# ele02_at.net
KiCad netlist of a schematic drawn in EAGLE
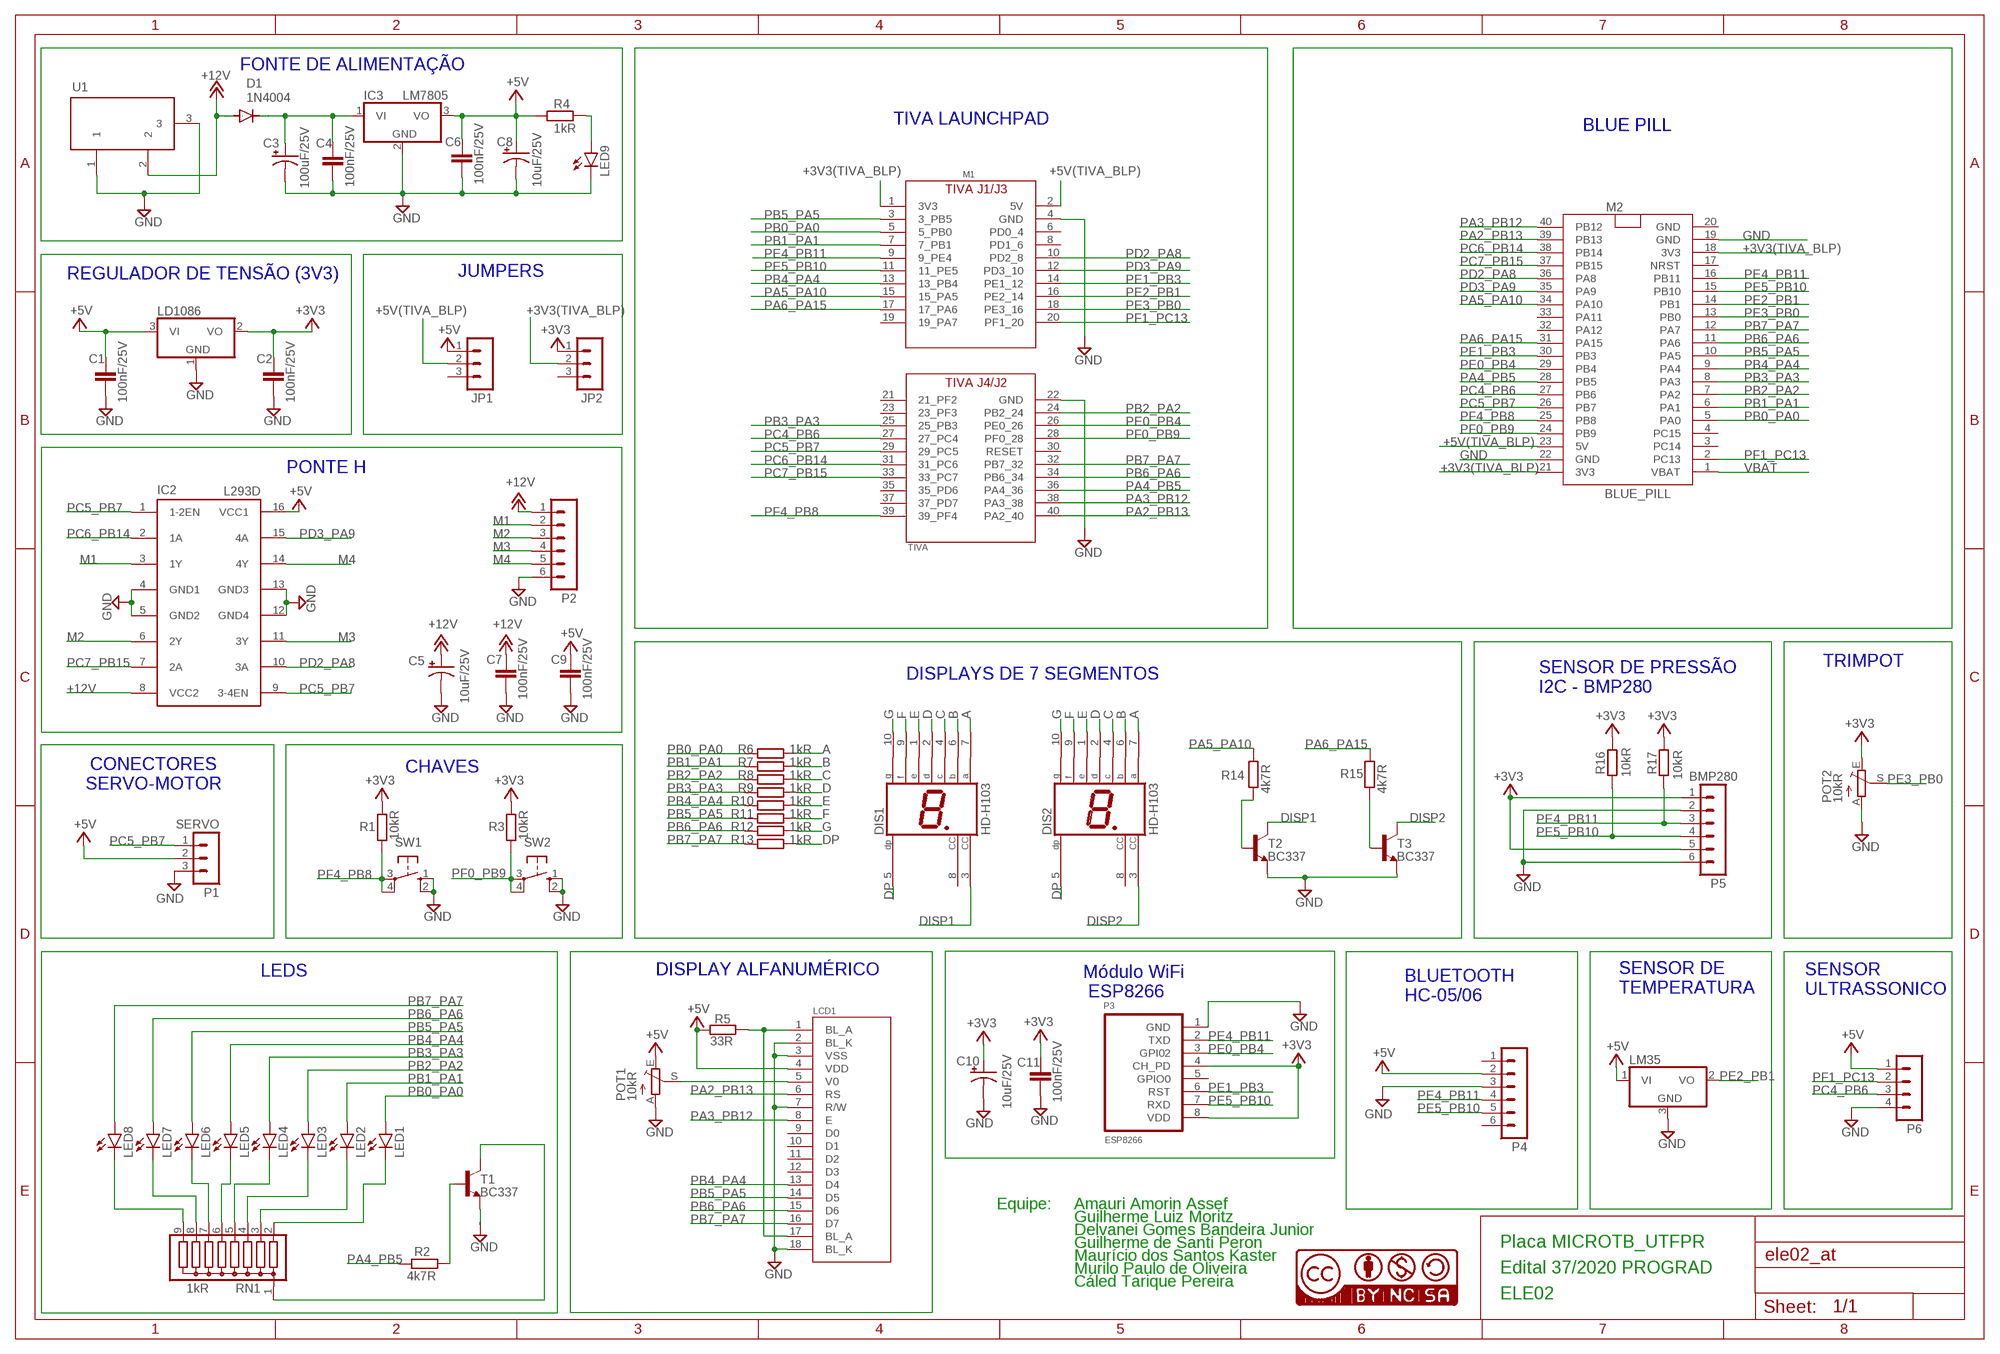
[diagram p0: schematic, sheet 1]

(export (version "E")
  (design (tool "Eeschema 10.0.6"))
  (components
    (comp (ref "C1")
      (value "100nF/25V")
      (footprint "eagle-import:C2.5-2")
      (libsource (lib "eagle-import") (part "C2.5/2"))
    )
    (comp (ref "C2")
      (value "100nF/25V")
      (footprint "eagle-import:C2.5-2")
      (libsource (lib "eagle-import") (part "C2.5/2"))
    )
    (comp (ref "C3")
      (value "100uF/25V")
      (footprint "eagle-import:E2,5-7")
      (libsource (lib "eagle-import") (part "CAPACITOR-PE2.5-7"))
    )
    (comp (ref "C4")
      (value "100nF/25V")
      (footprint "eagle-import:C2.5-2")
      (libsource (lib "eagle-import") (part "C2.5/2"))
    )
    (comp (ref "C5")
      (value "10uF/25V")
      (footprint "eagle-import:E2,5-6")
      (libsource (lib "eagle-import") (part "CAPACITOR-PE2.5-6"))
    )
    (comp (ref "C6")
      (value "100nF/25V")
      (footprint "eagle-import:C2.5-2")
      (libsource (lib "eagle-import") (part "C2.5/2"))
    )
    (comp (ref "C7")
      (value "100nF/25V")
      (footprint "eagle-import:C2.5-2")
      (libsource (lib "eagle-import") (part "C2.5/2"))
    )
    (comp (ref "C8")
      (value "10uF/25V")
      (footprint "eagle-import:E2,5-6")
      (libsource (lib "eagle-import") (part "CAPACITOR-PE2.5-6"))
    )
    (comp (ref "C9")
      (value "100nF/25V")
      (footprint "eagle-import:C2.5-2")
      (libsource (lib "eagle-import") (part "C2.5/2"))
    )
    (comp (ref "C10")
      (value "10uF/25V")
      (footprint "eagle-import:E2,5-6")
      (libsource (lib "eagle-import") (part "CAPACITOR-PE2.5-6"))
    )
    (comp (ref "C11")
      (value "100nF/25V")
      (footprint "eagle-import:C2.5-2")
      (libsource (lib "eagle-import") (part "C2.5/2"))
    )
    (comp (ref "D1")
      (value "1N4004")
      (footprint "eagle-import:DO41-10")
      (libsource (lib "eagle-import") (part "1N4004"))
    )
    (comp (ref "DIS1")
      (value "HD-H103")
      (footprint "eagle-import:HDSP-M")
      (libsource (lib "eagle-import") (part "HD-H103"))
    )
    (comp (ref "DIS2")
      (value "HD-H103")
      (footprint "eagle-import:HDSP-M")
      (libsource (lib "eagle-import") (part "HD-H103"))
    )
    (comp (ref "IC1")
      (value "LD1086")
      (footprint "eagle-import:LD1086")
      (libsource (lib "eagle-import") (part "LD1086TV05"))
    )
    (comp (ref "IC2")
      (value "L293D")
      (footprint "eagle-import:DIL16")
      (libsource (lib "eagle-import") (part "L293D"))
    )
    (comp (ref "IC3")
      (value "LM7805")
      (footprint "eagle-import:TO220V")
      (libsource (lib "eagle-import") (part "78TV6"))
    )
    (comp (ref "JP1")
      (value "JP")
      (footprint "eagle-import:MA03-1")
      (libsource (lib "eagle-import") (part "JUMP"))
    )
    (comp (ref "JP2")
      (value "JP")
      (footprint "eagle-import:MA03-1")
      (libsource (lib "eagle-import") (part "JUMP"))
    )
    (comp (ref "LCD1")
      (value "DISPLAY_LCDDISPLAY_LCD1")
      (footprint "eagle-import:DISPLAY_LCD_BL")
      (libsource (lib "eagle-import") (part "DISPLAY_LCDDISPLAY_LCD1"))
    )
    (comp (ref "LED1")
      (value "GREEN")
      (footprint "eagle-import:LED3MM")
      (libsource (lib "eagle-import") (part "LED3MM"))
    )
    (comp (ref "LED2")
      (value "GREEN")
      (footprint "eagle-import:LED3MM")
      (libsource (lib "eagle-import") (part "LED3MM"))
    )
    (comp (ref "LED3")
      (value "GREEN")
      (footprint "eagle-import:LED3MM")
      (libsource (lib "eagle-import") (part "LED3MM"))
    )
    (comp (ref "LED4")
      (value "GREEN")
      (footprint "eagle-import:LED3MM")
      (libsource (lib "eagle-import") (part "LED3MM"))
    )
    (comp (ref "LED5")
      (value "GREEN")
      (footprint "eagle-import:LED3MM")
      (libsource (lib "eagle-import") (part "LED3MM"))
    )
    (comp (ref "LED6")
      (value "GREEN")
      (footprint "eagle-import:LED3MM")
      (libsource (lib "eagle-import") (part "LED3MM"))
    )
    (comp (ref "LED7")
      (value "GREEN")
      (footprint "eagle-import:LED3MM")
      (libsource (lib "eagle-import") (part "LED3MM"))
    )
    (comp (ref "LED8")
      (value "GREEN")
      (footprint "eagle-import:LED3MM")
      (libsource (lib "eagle-import") (part "LED3MM"))
    )
    (comp (ref "LED9")
      (value "RED")
      (footprint "eagle-import:LED3MM")
      (libsource (lib "eagle-import") (part "LED3MM"))
    )
    (comp (ref "M1")
      (value "TIVA")
      (footprint "eagle-import:TIVA")
      (libsource (lib "eagle-import") (part "TIVA"))
    )
    (comp (ref "M2")
      (value "BLUE_PILL")
      (footprint "eagle-import:BLUE_PILL")
      (libsource (lib "eagle-import") (part "BLUE_PILL"))
    )
    (comp (ref "P1")
      (value "SERVO")
      (footprint "eagle-import:MA03-1")
      (libsource (lib "eagle-import") (part "CON3"))
    )
    (comp (ref "P2")
      (value "Motor")
      (footprint "eagle-import:HC_BLUETOOTH")
      (libsource (lib "eagle-import") (part "MA06-1"))
    )
    (comp (ref "P3")
      (value "ESP8266")
      (footprint "eagle-import:ESP8266")
      (libsource (lib "eagle-import") (part "ESP8266"))
    )
    (comp (ref "P4")
      (value "HC05_06")
      (footprint "eagle-import:HC_BLUETOOTH")
      (libsource (lib "eagle-import") (part "HC05_06"))
    )
    (comp (ref "P5")
      (value "BMP280")
      (footprint "eagle-import:BMP280")
      (libsource (lib "eagle-import") (part "BMP280"))
    )
    (comp (ref "P6")
      (value "HC-04")
      (footprint "eagle-import:HS-04")
      (libsource (lib "eagle-import") (part "HC-SR04US"))
    )
    (comp (ref "POT1")
      (value "10kR")
      (footprint "eagle-import:CA6V")
      (libsource (lib "eagle-import") (part "TRIM_EU-ELE02CA6V"))
    )
    (comp (ref "POT2")
      (value "10kR")
      (footprint "eagle-import:CIP20C-4MM")
      (libsource (lib "eagle-import") (part "TRIM_EU-CIP20C-4MM"))
    )
    (comp (ref "Q1")
      (value "LM35L05Z")
      (footprint "eagle-import:LM35")
      (libsource (lib "eagle-import") (part "LM35ZL05"))
    )
    (comp (ref "R1")
      (value "10kR")
      (footprint "eagle-import:0204_7")
      (libsource (lib "eagle-import") (part "R-EU_0204/7"))
    )
    (comp (ref "R2")
      (value "4k7R")
      (footprint "eagle-import:0204_7")
      (libsource (lib "eagle-import") (part "R-EU_0204/7"))
    )
    (comp (ref "R3")
      (value "10kR")
      (footprint "eagle-import:0204_7")
      (libsource (lib "eagle-import") (part "R-EU_0204/7"))
    )
    (comp (ref "R4")
      (value "1kR")
      (footprint "eagle-import:0204_7")
      (libsource (lib "eagle-import") (part "R-EU_0204/7"))
    )
    (comp (ref "R5")
      (value "33R")
      (footprint "eagle-import:0204_7")
      (libsource (lib "eagle-import") (part "R-EU_0204/7"))
    )
    (comp (ref "R6")
      (value "1kR")
      (footprint "eagle-import:0204_7")
      (libsource (lib "eagle-import") (part "R-EU_0204/7"))
    )
    (comp (ref "R7")
      (value "1kR")
      (footprint "eagle-import:0204_7")
      (libsource (lib "eagle-import") (part "R-EU_0204/7"))
    )
    (comp (ref "R8")
      (value "1kR")
      (footprint "eagle-import:0204_7")
      (libsource (lib "eagle-import") (part "R-EU_0204/7"))
    )
    (comp (ref "R9")
      (value "1kR")
      (footprint "eagle-import:0204_7")
      (libsource (lib "eagle-import") (part "R-EU_0204/7"))
    )
    (comp (ref "R10")
      (value "1kR")
      (footprint "eagle-import:0204_7")
      (libsource (lib "eagle-import") (part "R-EU_0204/7"))
    )
    (comp (ref "R11")
      (value "1kR")
      (footprint "eagle-import:0204_7")
      (libsource (lib "eagle-import") (part "R-EU_0204/7"))
    )
    (comp (ref "R12")
      (value "1kR")
      (footprint "eagle-import:0204_7")
      (libsource (lib "eagle-import") (part "R-EU_0204/7"))
    )
    (comp (ref "R13")
      (value "1kR")
      (footprint "eagle-import:0204_7")
      (libsource (lib "eagle-import") (part "R-EU_0204/7"))
    )
    (comp (ref "R14")
      (value "4k7R")
      (footprint "eagle-import:0204_7")
      (libsource (lib "eagle-import") (part "R-EU_0204/7"))
    )
    (comp (ref "R15")
      (value "4k7R")
      (footprint "eagle-import:0204_7")
      (libsource (lib "eagle-import") (part "R-EU_0204/7"))
    )
    (comp (ref "R16")
      (value "10kR")
      (footprint "eagle-import:0204_7")
      (libsource (lib "eagle-import") (part "R-EU_0204/7"))
    )
    (comp (ref "R17")
      (value "10kR")
      (footprint "eagle-import:0204_7")
      (libsource (lib "eagle-import") (part "R-EU_0204/7"))
    )
    (comp (ref "RN1")
      (value "1kR")
      (footprint "eagle-import:SIL9")
      (libsource (lib "eagle-import") (part "G08R"))
    )
    (comp (ref "SW1")
      (value "SW")
      (footprint "eagle-import:B3F-10XX")
      (fields (field (name "MPN") "B3F-1000"))
      (libsource (lib "eagle-import") (part "10-XX"))
    )
    (comp (ref "SW2")
      (value "SW")
      (footprint "eagle-import:B3F-10XX")
      (fields (field (name "MPN") "B3F-1000"))
      (libsource (lib "eagle-import") (part "10-XX"))
    )
    (comp (ref "T1")
      (value "BC337")
      (footprint "eagle-import:TO92-CBE")
      (libsource (lib "eagle-import") (part "-NPN-TO92-CBEBC337-16"))
    )
    (comp (ref "T2")
      (value "BC337")
      (footprint "eagle-import:TO92-CBE")
      (libsource (lib "eagle-import") (part "-NPN-TO92-CBEBC337-16"))
    )
    (comp (ref "T3")
      (value "BC337")
      (footprint "eagle-import:TO92-CBE")
      (libsource (lib "eagle-import") (part "-NPN-TO92-CBEBC337-16"))
    )
    (comp (ref "U$1")
      (value "CC-NC-BC")
      (footprint "eagle-import:CC-NC-BY")
      (libsource (lib "eagle-import") (part "CC-NC-BC"))
    )
    (comp (ref "U1")
      (value "POWERSUPPLY_DC21MMX")
      (footprint "eagle-import:POWERSUPPLY_DC-21MM")
      (libsource (lib "eagle-import") (part "POWERSUPPLY_DC21MMX"))
    )
  )
  (nets
    (net (code "1") (name "+3V3") (class "Default")
      (node (ref "C10") (pin "+") (pinfunction "+_+") (pintype "passive"))
      (node (ref "C11") (pin "1") (pinfunction "1_1") (pintype "passive"))
      (node (ref "C2") (pin "1") (pinfunction "1_1") (pintype "passive"))
      (node (ref "IC1") (pin "2") (pinfunction "VO_2") (pintype "passive"))
      (node (ref "JP2") (pin "1") (pinfunction "1_1") (pintype "passive"))
      (node (ref "P3") (pin "4") (pinfunction "CH_PD_4") (pintype "bidirectional"))
      (node (ref "P3") (pin "8") (pinfunction "VDD_8") (pintype "bidirectional"))
      (node (ref "P5") (pin "1") (pinfunction "1_1") (pintype "passive"))
      (node (ref "P5") (pin "5") (pinfunction "5_5") (pintype "passive"))
      (node (ref "POT2") (pin "E") (pinfunction "E_E") (pintype "passive"))
      (node (ref "R1") (pin "2") (pinfunction "2_2") (pintype "passive"))
      (node (ref "R16") (pin "2") (pinfunction "2_2") (pintype "passive"))
      (node (ref "R17") (pin "2") (pinfunction "2_2") (pintype "passive"))
      (node (ref "R3") (pin "2") (pinfunction "2_2") (pintype "passive"))
    )
    (net (code "2") (name "+5V") (class "Default")
      (node (ref "C1") (pin "1") (pinfunction "1_1") (pintype "passive"))
      (node (ref "C6") (pin "1") (pinfunction "1_1") (pintype "passive"))
      (node (ref "C8") (pin "+") (pinfunction "+_+") (pintype "passive"))
      (node (ref "C9") (pin "1") (pinfunction "1_1") (pintype "passive"))
      (node (ref "IC1") (pin "3") (pinfunction "VI_3") (pintype "input"))
      (node (ref "IC2") (pin "16") (pinfunction "VCC1_16") (pintype "power_in"))
      (node (ref "IC3") (pin "3") (pinfunction "VO_3") (pintype "passive"))
      (node (ref "JP1") (pin "1") (pinfunction "1_1") (pintype "passive"))
      (node (ref "LCD1") (pin "4") (pinfunction "VDD_4") (pintype "bidirectional"))
      (node (ref "P1") (pin "2") (pinfunction "2_2") (pintype "passive"))
      (node (ref "P4") (pin "2") (pinfunction "2_2") (pintype "passive"))
      (node (ref "P6") (pin "1") (pinfunction "1_1") (pintype "passive"))
      (node (ref "POT1") (pin "E") (pinfunction "E_E") (pintype "passive"))
      (node (ref "Q1") (pin "1") (pinfunction "VI_1") (pintype "input"))
      (node (ref "R4") (pin "1") (pinfunction "1_1") (pintype "passive"))
      (node (ref "R5") (pin "2") (pinfunction "2_2") (pintype "passive"))
    )
    (net (code "3") (name "+12V") (class "Default")
      (node (ref "C5") (pin "+") (pinfunction "+_+") (pintype "passive"))
      (node (ref "C7") (pin "1") (pinfunction "1_1") (pintype "passive"))
      (node (ref "D1") (pin "A") (pinfunction "A_A") (pintype "passive"))
      (node (ref "IC2") (pin "8") (pinfunction "VCC2_8") (pintype "power_in"))
      (node (ref "P2") (pin "1") (pinfunction "1_1") (pintype "passive"))
      (node (ref "U1") (pin "2") (pinfunction "2_2") (pintype "power_in"))
    )
    (net (code "4") (name "/+3V3(TIVA_BLP)") (class "Default")
      (node (ref "JP2") (pin "2") (pinfunction "2_2") (pintype "passive"))
      (node (ref "M1") (pin "1") (pinfunction "3V3_1") (pintype "bidirectional"))
      (node (ref "M2") (pin "18") (pinfunction "3V3_18") (pintype "bidirectional"))
      (node (ref "M2") (pin "21") (pinfunction "3V3_21") (pintype "bidirectional"))
    )
    (net (code "5") (name "/+5V(TIVA_BLP)") (class "Default")
      (node (ref "JP1") (pin "2") (pinfunction "2_2") (pintype "passive"))
      (node (ref "M1") (pin "2") (pinfunction "5V_2") (pintype "bidirectional"))
      (node (ref "M2") (pin "23") (pinfunction "5V_23") (pintype "bidirectional"))
    )
    (net (code "6") (name "/A") (class "Default")
      (node (ref "DIS1") (pin "7") (pinfunction "A_7") (pintype "passive"))
      (node (ref "DIS2") (pin "7") (pinfunction "A_7") (pintype "passive"))
      (node (ref "R6") (pin "1") (pinfunction "1_1") (pintype "passive"))
    )
    (net (code "7") (name "/B") (class "Default")
      (node (ref "DIS1") (pin "6") (pinfunction "B_6") (pintype "passive"))
      (node (ref "DIS2") (pin "6") (pinfunction "B_6") (pintype "passive"))
      (node (ref "R7") (pin "1") (pinfunction "1_1") (pintype "passive"))
    )
    (net (code "8") (name "/C") (class "Default")
      (node (ref "DIS1") (pin "4") (pinfunction "C_4") (pintype "passive"))
      (node (ref "DIS2") (pin "4") (pinfunction "C_4") (pintype "passive"))
      (node (ref "R8") (pin "1") (pinfunction "1_1") (pintype "passive"))
    )
    (net (code "9") (name "/D") (class "Default")
      (node (ref "DIS1") (pin "2") (pinfunction "D_2") (pintype "passive"))
      (node (ref "DIS2") (pin "2") (pinfunction "D_2") (pintype "passive"))
      (node (ref "R9") (pin "1") (pinfunction "1_1") (pintype "passive"))
    )
    (net (code "10") (name "/DISP1") (class "Default")
      (node (ref "DIS1") (pin "3") (pinfunction "CC_3") (pintype "passive"))
      (node (ref "T2") (pin "C") (pinfunction "C_C") (pintype "passive"))
    )
    (net (code "11") (name "/DISP2") (class "Default")
      (node (ref "DIS2") (pin "3") (pinfunction "CC_3") (pintype "passive"))
      (node (ref "T3") (pin "C") (pinfunction "C_C") (pintype "passive"))
    )
    (net (code "12") (name "/DP") (class "Default")
      (node (ref "DIS1") (pin "5") (pinfunction "DP_5") (pintype "passive"))
      (node (ref "DIS2") (pin "5") (pinfunction "DP_5") (pintype "passive"))
      (node (ref "R13") (pin "1") (pinfunction "1_1") (pintype "passive"))
    )
    (net (code "13") (name "/E") (class "Default")
      (node (ref "DIS1") (pin "1") (pinfunction "E_1") (pintype "passive"))
      (node (ref "DIS2") (pin "1") (pinfunction "E_1") (pintype "passive"))
      (node (ref "R10") (pin "1") (pinfunction "1_1") (pintype "passive"))
    )
    (net (code "14") (name "/F") (class "Default")
      (node (ref "DIS1") (pin "9") (pinfunction "F_9") (pintype "passive"))
      (node (ref "DIS2") (pin "9") (pinfunction "F_9") (pintype "passive"))
      (node (ref "R11") (pin "1") (pinfunction "1_1") (pintype "passive"))
    )
    (net (code "15") (name "/G") (class "Default")
      (node (ref "DIS1") (pin "10") (pinfunction "G_10") (pintype "passive"))
      (node (ref "DIS2") (pin "10") (pinfunction "G_10") (pintype "passive"))
      (node (ref "R12") (pin "1") (pinfunction "1_1") (pintype "passive"))
    )
    (net (code "16") (name "/M1") (class "Default")
      (node (ref "IC2") (pin "3") (pinfunction "1Y_3") (pintype "output"))
      (node (ref "P2") (pin "2") (pinfunction "2_2") (pintype "passive"))
    )
    (net (code "17") (name "/M2") (class "Default")
      (node (ref "IC2") (pin "6") (pinfunction "2Y_6") (pintype "output"))
      (node (ref "P2") (pin "3") (pinfunction "3_3") (pintype "passive"))
    )
    (net (code "18") (name "/M3") (class "Default")
      (node (ref "IC2") (pin "11") (pinfunction "3Y_11") (pintype "output"))
      (node (ref "P2") (pin "4") (pinfunction "4_4") (pintype "passive"))
    )
    (net (code "19") (name "/M4") (class "Default")
      (node (ref "IC2") (pin "14") (pinfunction "4Y_14") (pintype "output"))
      (node (ref "P2") (pin "5") (pinfunction "5_5") (pintype "passive"))
    )
    (net (code "20") (name "/PA2_PB13") (class "Default")
      (node (ref "LCD1") (pin "6") (pinfunction "RS_6") (pintype "bidirectional"))
      (node (ref "M1") (pin "40") (pinfunction "PA2_40_40") (pintype "bidirectional"))
      (node (ref "M2") (pin "39") (pinfunction "PB13_39") (pintype "bidirectional"))
    )
    (net (code "21") (name "/PA3_PB12") (class "Default")
      (node (ref "LCD1") (pin "8") (pinfunction "E_8") (pintype "bidirectional"))
      (node (ref "M1") (pin "38") (pinfunction "PA3_38_38") (pintype "input"))
      (node (ref "M2") (pin "40") (pinfunction "PB12_40") (pintype "bidirectional"))
    )
    (net (code "22") (name "/PA4_PB5") (class "Default")
      (node (ref "M1") (pin "36") (pinfunction "PA4_36_36") (pintype "input"))
      (node (ref "M2") (pin "28") (pinfunction "PB5_28") (pintype "bidirectional"))
      (node (ref "R2") (pin "1") (pinfunction "1_1") (pintype "passive"))
    )
    (net (code "23") (name "/PA5_PA10") (class "Default")
      (node (ref "M1") (pin "15") (pinfunction "15_PA5_15") (pintype "bidirectional"))
      (node (ref "M2") (pin "34") (pinfunction "PA10_34") (pintype "bidirectional"))
      (node (ref "R14") (pin "2") (pinfunction "2_2") (pintype "passive"))
    )
    (net (code "24") (name "/PA6_PA15") (class "Default")
      (node (ref "M1") (pin "17") (pinfunction "17_PA6_17") (pintype "bidirectional"))
      (node (ref "M2") (pin "31") (pinfunction "PA15_31") (pintype "bidirectional"))
      (node (ref "R15") (pin "2") (pinfunction "2_2") (pintype "passive"))
    )
    (net (code "25") (name "/PB0_PA0") (class "Default")
      (node (ref "LED1") (pin "A") (pinfunction "A_A") (pintype "passive"))
      (node (ref "M1") (pin "5") (pinfunction "5_PB0_5") (pintype "bidirectional"))
      (node (ref "M2") (pin "5") (pinfunction "PA0_5") (pintype "bidirectional"))
      (node (ref "R6") (pin "2") (pinfunction "2_2") (pintype "passive"))
    )
    (net (code "26") (name "/PB1_PA1") (class "Default")
      (node (ref "LED2") (pin "A") (pinfunction "A_A") (pintype "passive"))
      (node (ref "M1") (pin "7") (pinfunction "7_PB1_7") (pintype "bidirectional"))
      (node (ref "M2") (pin "6") (pinfunction "PA1_6") (pintype "bidirectional"))
      (node (ref "R7") (pin "2") (pinfunction "2_2") (pintype "passive"))
    )
    (net (code "27") (name "/PB2_PA2") (class "Default")
      (node (ref "LED3") (pin "A") (pinfunction "A_A") (pintype "passive"))
      (node (ref "M1") (pin "24") (pinfunction "PB2_24_24") (pintype "input"))
      (node (ref "M2") (pin "7") (pinfunction "PA2_7") (pintype "bidirectional"))
      (node (ref "R8") (pin "2") (pinfunction "2_2") (pintype "passive"))
    )
    (net (code "28") (name "/PB3_PA3") (class "Default")
      (node (ref "LED4") (pin "A") (pinfunction "A_A") (pintype "passive"))
      (node (ref "M1") (pin "25") (pinfunction "25_PB3_25") (pintype "bidirectional"))
      (node (ref "M2") (pin "8") (pinfunction "PA3_8") (pintype "bidirectional"))
      (node (ref "R9") (pin "2") (pinfunction "2_2") (pintype "passive"))
    )
    (net (code "29") (name "/PB4_PA4") (class "Default")
      (node (ref "LCD1") (pin "13") (pinfunction "D4_13") (pintype "bidirectional"))
      (node (ref "LED5") (pin "A") (pinfunction "A_A") (pintype "passive"))
      (node (ref "M1") (pin "13") (pinfunction "13_PB4_13") (pintype "bidirectional"))
      (node (ref "M2") (pin "9") (pinfunction "PA4_9") (pintype "bidirectional"))
      (node (ref "R10") (pin "2") (pinfunction "2_2") (pintype "passive"))
    )
    (net (code "30") (name "/PB5_PA5") (class "Default")
      (node (ref "LCD1") (pin "14") (pinfunction "D5_14") (pintype "bidirectional"))
      (node (ref "LED6") (pin "A") (pinfunction "A_A") (pintype "passive"))
      (node (ref "M1") (pin "3") (pinfunction "3_PB5_3") (pintype "bidirectional"))
      (node (ref "M2") (pin "10") (pinfunction "PA5_10") (pintype "bidirectional"))
      (node (ref "R11") (pin "2") (pinfunction "2_2") (pintype "passive"))
    )
    (net (code "31") (name "/PB6_PA6") (class "Default")
      (node (ref "LCD1") (pin "15") (pinfunction "D6_15") (pintype "bidirectional"))
      (node (ref "LED7") (pin "A") (pinfunction "A_A") (pintype "passive"))
      (node (ref "M1") (pin "34") (pinfunction "PB6_34_34") (pintype "bidirectional"))
      (node (ref "M2") (pin "11") (pinfunction "PA6_11") (pintype "bidirectional"))
      (node (ref "R12") (pin "2") (pinfunction "2_2") (pintype "passive"))
    )
    (net (code "32") (name "/PB7_PA7") (class "Default")
      (node (ref "LCD1") (pin "16") (pinfunction "D7_16") (pintype "bidirectional"))
      (node (ref "LED8") (pin "A") (pinfunction "A_A") (pintype "passive"))
      (node (ref "M1") (pin "32") (pinfunction "PB7_32_32") (pintype "bidirectional"))
      (node (ref "M2") (pin "12") (pinfunction "PA7_12") (pintype "bidirectional"))
      (node (ref "R13") (pin "2") (pinfunction "2_2") (pintype "passive"))
    )
    (net (code "33") (name "/PC4_PB6") (class "Default")
      (node (ref "M1") (pin "27") (pinfunction "27_PC4_27") (pintype "bidirectional"))
      (node (ref "M2") (pin "27") (pinfunction "PB6_27") (pintype "bidirectional"))
      (node (ref "P6") (pin "3") (pinfunction "3_3") (pintype "passive"))
    )
    (net (code "34") (name "/PC5_PB7") (class "Default")
      (node (ref "IC2") (pin "1") (pinfunction "1-2EN_1") (pintype "input"))
      (node (ref "IC2") (pin "9") (pinfunction "3-4EN_9") (pintype "input"))
      (node (ref "M1") (pin "29") (pinfunction "29_PC5_29") (pintype "input"))
      (node (ref "M2") (pin "26") (pinfunction "PB7_26") (pintype "bidirectional"))
      (node (ref "P1") (pin "1") (pinfunction "1_1") (pintype "passive"))
    )
    (net (code "35") (name "/PC6_PB14") (class "Default")
      (node (ref "IC2") (pin "2") (pinfunction "1A_2") (pintype "input"))
      (node (ref "M1") (pin "31") (pinfunction "31_PC6_31") (pintype "bidirectional"))
      (node (ref "M2") (pin "38") (pinfunction "PB14_38") (pintype "bidirectional"))
    )
    (net (code "36") (name "/PC7_PB15") (class "Default")
      (node (ref "IC2") (pin "7") (pinfunction "2A_7") (pintype "input"))
      (node (ref "M1") (pin "33") (pinfunction "33_PC7_33") (pintype "bidirectional"))
      (node (ref "M2") (pin "37") (pinfunction "PB15_37") (pintype "bidirectional"))
    )
    (net (code "37") (name "/PD2_PA8") (class "Default")
      (node (ref "IC2") (pin "10") (pinfunction "3A_10") (pintype "input"))
      (node (ref "M1") (pin "10") (pinfunction "PD2_8_10") (pintype "bidirectional"))
      (node (ref "M2") (pin "36") (pinfunction "PA8_36") (pintype "bidirectional"))
    )
    (net (code "38") (name "/PD3_PA9") (class "Default")
      (node (ref "IC2") (pin "15") (pinfunction "4A_15") (pintype "input"))
      (node (ref "M1") (pin "12") (pinfunction "PD3_10_12") (pintype "bidirectional"))
      (node (ref "M2") (pin "35") (pinfunction "PA9_35") (pintype "bidirectional"))
    )
    (net (code "39") (name "/PE0_PB4") (class "Default")
      (node (ref "M1") (pin "26") (pinfunction "PE0_26_26") (pintype "bidirectional"))
      (node (ref "M2") (pin "29") (pinfunction "PB4_29") (pintype "bidirectional"))
      (node (ref "P3") (pin "3") (pinfunction "GPI02_3") (pintype "bidirectional"))
    )
    (net (code "40") (name "/PE1_PB3") (class "Default")
      (node (ref "M1") (pin "14") (pinfunction "PE1_12_14") (pintype "bidirectional"))
      (node (ref "M2") (pin "30") (pinfunction "PB3_30") (pintype "bidirectional"))
      (node (ref "P3") (pin "6") (pinfunction "RST_6") (pintype "bidirectional"))
    )
    (net (code "41") (name "/PE2_PB1") (class "Default")
      (node (ref "M1") (pin "16") (pinfunction "PE2_14_16") (pintype "bidirectional"))
      (node (ref "M2") (pin "14") (pinfunction "PB1_14") (pintype "bidirectional"))
      (node (ref "Q1") (pin "2") (pinfunction "VO_2") (pintype "passive"))
    )
    (net (code "42") (name "/PE3_PB0") (class "Default")
      (node (ref "M1") (pin "18") (pinfunction "PE3_16_18") (pintype "bidirectional"))
      (node (ref "M2") (pin "13") (pinfunction "PB0_13") (pintype "bidirectional"))
      (node (ref "POT2") (pin "S") (pinfunction "S_S") (pintype "passive"))
    )
    (net (code "43") (name "/PE4_PB11") (class "Default")
      (node (ref "M1") (pin "9") (pinfunction "9_PE4_9") (pintype "bidirectional"))
      (node (ref "M2") (pin "16") (pinfunction "PB11_16") (pintype "bidirectional"))
      (node (ref "P3") (pin "2") (pinfunction "TXD_2") (pintype "bidirectional"))
      (node (ref "P4") (pin "4") (pinfunction "4_4") (pintype "passive"))
      (node (ref "P5") (pin "3") (pinfunction "3_3") (pintype "passive"))
      (node (ref "R17") (pin "1") (pinfunction "1_1") (pintype "passive"))
    )
    (net (code "44") (name "/PE5_PB10") (class "Default")
      (node (ref "M1") (pin "11") (pinfunction "11_PE5_11") (pintype "bidirectional"))
      (node (ref "M2") (pin "15") (pinfunction "PB10_15") (pintype "bidirectional"))
      (node (ref "P3") (pin "7") (pinfunction "RXD_7") (pintype "bidirectional"))
      (node (ref "P4") (pin "5") (pinfunction "5_5") (pintype "passive"))
      (node (ref "P5") (pin "4") (pinfunction "4_4") (pintype "passive"))
      (node (ref "R16") (pin "1") (pinfunction "1_1") (pintype "passive"))
    )
    (net (code "45") (name "/PF0_PB9") (class "Default")
      (node (ref "M1") (pin "28") (pinfunction "PF0_28_28") (pintype "bidirectional"))
      (node (ref "M2") (pin "24") (pinfunction "PB9_24") (pintype "bidirectional"))
      (node (ref "R3") (pin "1") (pinfunction "1_1") (pintype "passive"))
      (node (ref "SW2") (pin "3") (pinfunction "P_3") (pintype "passive"))
      (node (ref "SW2") (pin "4") (pinfunction "P1_4") (pintype "passive"))
    )
    (net (code "46") (name "/PF1_PC13") (class "Default")
      (node (ref "M1") (pin "20") (pinfunction "PF1_20_20") (pintype "bidirectional"))
      (node (ref "M2") (pin "2") (pinfunction "PC13_2") (pintype "bidirectional"))
      (node (ref "P6") (pin "2") (pinfunction "2_2") (pintype "passive"))
    )
    (net (code "47") (name "/PF4_PB8") (class "Default")
      (node (ref "M1") (pin "39") (pinfunction "39_PF4_39") (pintype "bidirectional"))
      (node (ref "M2") (pin "25") (pinfunction "PB8_25") (pintype "bidirectional"))
      (node (ref "R1") (pin "1") (pinfunction "1_1") (pintype "passive"))
      (node (ref "SW1") (pin "3") (pinfunction "P_3") (pintype "passive"))
      (node (ref "SW1") (pin "4") (pinfunction "P1_4") (pintype "passive"))
    )
    (net (code "48") (name "/VBAT") (class "Default")
      (node (ref "M2") (pin "1") (pinfunction "VBAT_1") (pintype "bidirectional"))
    )
    (net (code "49") (name "GND") (class "Default")
      (node (ref "C1") (pin "2") (pinfunction "2_2") (pintype "passive"))
      (node (ref "C10") (pin "-") (pinfunction "-_-") (pintype "passive"))
      (node (ref "C11") (pin "2") (pinfunction "2_2") (pintype "passive"))
      (node (ref "C2") (pin "2") (pinfunction "2_2") (pintype "passive"))
      (node (ref "C3") (pin "-") (pinfunction "-_-") (pintype "passive"))
      (node (ref "C4") (pin "2") (pinfunction "2_2") (pintype "passive"))
      (node (ref "C5") (pin "-") (pinfunction "-_-") (pintype "passive"))
      (node (ref "C6") (pin "2") (pinfunction "2_2") (pintype "passive"))
      (node (ref "C7") (pin "2") (pinfunction "2_2") (pintype "passive"))
      (node (ref "C8") (pin "-") (pinfunction "-_-") (pintype "passive"))
      (node (ref "C9") (pin "2") (pinfunction "2_2") (pintype "passive"))
      (node (ref "IC1") (pin "1") (pinfunction "GND_1") (pintype "passive"))
      (node (ref "IC2") (pin "12") (pinfunction "GND4_12") (pintype "power_in"))
      (node (ref "IC2") (pin "13") (pinfunction "GND3_13") (pintype "power_in"))
      (node (ref "IC2") (pin "4") (pinfunction "GND1_4") (pintype "power_in"))
      (node (ref "IC2") (pin "5") (pinfunction "GND2_5") (pintype "power_in"))
      (node (ref "IC3") (pin "2") (pinfunction "GND_2") (pintype "passive"))
      (node (ref "LCD1") (pin "18") (pinfunction "BL_K_18") (pintype "bidirectional"))
      (node (ref "LCD1") (pin "2") (pinfunction "BL_K_2") (pintype "bidirectional"))
      (node (ref "LCD1") (pin "3") (pinfunction "VSS_3") (pintype "bidirectional"))
      (node (ref "LCD1") (pin "7") (pinfunction "R/W_7") (pintype "bidirectional"))
      (node (ref "LED9") (pin "K") (pinfunction "C_K") (pintype "passive"))
      (node (ref "M1") (pin "22") (pinfunction "GND_22") (pintype "input"))
      (node (ref "M1") (pin "4") (pinfunction "GND_4") (pintype "bidirectional"))
      (node (ref "M2") (pin "19") (pinfunction "GND_19") (pintype "bidirectional"))
      (node (ref "M2") (pin "22") (pinfunction "GND_22") (pintype "bidirectional"))
      (node (ref "P1") (pin "3") (pinfunction "3_3") (pintype "passive"))
      (node (ref "P2") (pin "6") (pinfunction "6_6") (pintype "passive"))
      (node (ref "P3") (pin "1") (pinfunction "GND_1") (pintype "bidirectional"))
      (node (ref "P4") (pin "3") (pinfunction "3_3") (pintype "passive"))
      (node (ref "P5") (pin "2") (pinfunction "2_2") (pintype "passive"))
      (node (ref "P5") (pin "6") (pinfunction "6_6") (pintype "passive"))
      (node (ref "P6") (pin "4") (pinfunction "4_4") (pintype "passive"))
      (node (ref "POT1") (pin "A") (pinfunction "A_A") (pintype "passive"))
      (node (ref "POT2") (pin "A") (pinfunction "A_A") (pintype "passive"))
      (node (ref "Q1") (pin "3") (pinfunction "GND_3") (pintype "passive"))
      (node (ref "SW1") (pin "1") (pinfunction "S_1") (pintype "passive"))
      (node (ref "SW1") (pin "2") (pinfunction "S1_2") (pintype "passive"))
      (node (ref "SW2") (pin "1") (pinfunction "S_1") (pintype "passive"))
      (node (ref "SW2") (pin "2") (pinfunction "S1_2") (pintype "passive"))
      (node (ref "T1") (pin "E") (pinfunction "E_E") (pintype "passive"))
      (node (ref "T2") (pin "E") (pinfunction "E_E") (pintype "passive"))
      (node (ref "T3") (pin "E") (pinfunction "E_E") (pintype "passive"))
      (node (ref "U1") (pin "1") (pinfunction "1_1") (pintype "power_in"))
      (node (ref "U1") (pin "3") (pinfunction "3_3") (pintype "power_in"))
    )
    (net (code "50") (name "Net-(IC3-VI)") (class "Default")
      (node (ref "C3") (pin "+") (pinfunction "+_+") (pintype "passive"))
      (node (ref "C4") (pin "1") (pinfunction "1_1") (pintype "passive"))
      (node (ref "D1") (pin "C") (pinfunction "C_C") (pintype "passive"))
      (node (ref "IC3") (pin "1") (pinfunction "VI_1") (pintype "input"))
    )
    (net (code "51") (name "Net-(LCD1-BL_A-Pad1)") (class "Default")
      (node (ref "LCD1") (pin "1") (pinfunction "BL_A_1") (pintype "bidirectional"))
      (node (ref "LCD1") (pin "17") (pinfunction "BL_A_17") (pintype "bidirectional"))
      (node (ref "R5") (pin "1") (pinfunction "1_1") (pintype "passive"))
    )
    (net (code "52") (name "Net-(LCD1-V0)") (class "Default")
      (node (ref "LCD1") (pin "5") (pinfunction "V0_5") (pintype "bidirectional"))
      (node (ref "POT1") (pin "S") (pinfunction "S_S") (pintype "passive"))
    )
    (net (code "53") (name "Net-(LED1-C)") (class "Default")
      (node (ref "LED1") (pin "K") (pinfunction "C_K") (pintype "passive"))
      (node (ref "RN1") (pin "2") (pinfunction "2_2") (pintype "passive"))
    )
    (net (code "54") (name "Net-(LED2-C)") (class "Default")
      (node (ref "LED2") (pin "K") (pinfunction "C_K") (pintype "passive"))
      (node (ref "RN1") (pin "3") (pinfunction "3_3") (pintype "passive"))
    )
    (net (code "55") (name "Net-(LED3-C)") (class "Default")
      (node (ref "LED3") (pin "K") (pinfunction "C_K") (pintype "passive"))
      (node (ref "RN1") (pin "4") (pinfunction "4_4") (pintype "passive"))
    )
    (net (code "56") (name "Net-(LED4-C)") (class "Default")
      (node (ref "LED4") (pin "K") (pinfunction "C_K") (pintype "passive"))
      (node (ref "RN1") (pin "5") (pinfunction "5_5") (pintype "passive"))
    )
    (net (code "57") (name "Net-(LED5-C)") (class "Default")
      (node (ref "LED5") (pin "K") (pinfunction "C_K") (pintype "passive"))
      (node (ref "RN1") (pin "6") (pinfunction "6_6") (pintype "passive"))
    )
    (net (code "58") (name "Net-(LED6-C)") (class "Default")
      (node (ref "LED6") (pin "K") (pinfunction "C_K") (pintype "passive"))
      (node (ref "RN1") (pin "7") (pinfunction "7_7") (pintype "passive"))
    )
    (net (code "59") (name "Net-(LED7-C)") (class "Default")
      (node (ref "LED7") (pin "K") (pinfunction "C_K") (pintype "passive"))
      (node (ref "RN1") (pin "8") (pinfunction "8_8") (pintype "passive"))
    )
    (net (code "60") (name "Net-(LED8-C)") (class "Default")
      (node (ref "LED8") (pin "K") (pinfunction "C_K") (pintype "passive"))
      (node (ref "RN1") (pin "9") (pinfunction "9_9") (pintype "passive"))
    )
    (net (code "61") (name "Net-(LED9-PadA)") (class "Default")
      (node (ref "LED9") (pin "A") (pinfunction "A_A") (pintype "passive"))
      (node (ref "R4") (pin "2") (pinfunction "2_2") (pintype "passive"))
    )
    (net (code "62") (name "Net-(R2-Pad2)") (class "Default")
      (node (ref "R2") (pin "2") (pinfunction "2_2") (pintype "passive"))
      (node (ref "T1") (pin "B") (pinfunction "B_B") (pintype "passive"))
    )
    (net (code "63") (name "Net-(R14-Pad1)") (class "Default")
      (node (ref "R14") (pin "1") (pinfunction "1_1") (pintype "passive"))
      (node (ref "T2") (pin "B") (pinfunction "B_B") (pintype "passive"))
    )
    (net (code "64") (name "Net-(R15-Pad1)") (class "Default")
      (node (ref "R15") (pin "1") (pinfunction "1_1") (pintype "passive"))
      (node (ref "T3") (pin "B") (pinfunction "B_B") (pintype "passive"))
    )
    (net (code "65") (name "Net-(RN1-Pad1)") (class "Default")
      (node (ref "RN1") (pin "1") (pinfunction "1_1") (pintype "passive"))
      (node (ref "T1") (pin "C") (pinfunction "C_C") (pintype "passive"))
    )
    (net (code "66") (name "unconnected-(DIS1-CC-Pad8)") (class "Default")
      (node (ref "DIS1") (pin "8") (pinfunction "CC_8") (pintype "passive"))
    )
    (net (code "67") (name "unconnected-(DIS2-CC-Pad8)") (class "Default")
      (node (ref "DIS2") (pin "8") (pinfunction "CC_8") (pintype "passive"))
    )
    (net (code "68") (name "unconnected-(JP1-Pad3)") (class "Default")
      (node (ref "JP1") (pin "3") (pinfunction "3_3") (pintype "no_connect"))
    )
    (net (code "69") (name "unconnected-(JP2-Pad3)") (class "Default")
      (node (ref "JP2") (pin "3") (pinfunction "3_3") (pintype "no_connect"))
    )
    (net (code "70") (name "unconnected-(LCD1-D0-Pad9)") (class "Default")
      (node (ref "LCD1") (pin "9") (pinfunction "D0_9") (pintype "no_connect"))
    )
    (net (code "71") (name "unconnected-(LCD1-D1-Pad10)") (class "Default")
      (node (ref "LCD1") (pin "10") (pinfunction "D1_10") (pintype "no_connect"))
    )
    (net (code "72") (name "unconnected-(LCD1-D2-Pad11)") (class "Default")
      (node (ref "LCD1") (pin "11") (pinfunction "D2_11") (pintype "no_connect"))
    )
    (net (code "73") (name "unconnected-(LCD1-D3-Pad12)") (class "Default")
      (node (ref "LCD1") (pin "12") (pinfunction "D3_12") (pintype "no_connect"))
    )
    (net (code "74") (name "unconnected-(M1-19_PA7-Pad19)") (class "Default")
      (node (ref "M1") (pin "19") (pinfunction "19_PA7_19") (pintype "no_connect"))
    )
    (net (code "75") (name "unconnected-(M1-21_PF2-Pad21)") (class "Default")
      (node (ref "M1") (pin "21") (pinfunction "21_PF2_21") (pintype "no_connect"))
    )
    (net (code "76") (name "unconnected-(M1-23_PF3-Pad23)") (class "Default")
      (node (ref "M1") (pin "23") (pinfunction "23_PF3_23") (pintype "no_connect"))
    )
    (net (code "77") (name "unconnected-(M1-35_PD6-Pad35)") (class "Default")
      (node (ref "M1") (pin "35") (pinfunction "35_PD6_35") (pintype "no_connect"))
    )
    (net (code "78") (name "unconnected-(M1-37_PD7-Pad37)") (class "Default")
      (node (ref "M1") (pin "37") (pinfunction "37_PD7_37") (pintype "no_connect"))
    )
    (net (code "79") (name "unconnected-(M1-PD0_4-Pad6)") (class "Default")
      (node (ref "M1") (pin "6") (pinfunction "PD0_4_6") (pintype "no_connect"))
    )
    (net (code "80") (name "unconnected-(M1-PD1_6-Pad8)") (class "Default")
      (node (ref "M1") (pin "8") (pinfunction "PD1_6_8") (pintype "no_connect"))
    )
    (net (code "81") (name "unconnected-(M1-RESET-Pad30)") (class "Default")
      (node (ref "M1") (pin "30") (pinfunction "RESET_30") (pintype "no_connect"))
    )
    (net (code "82") (name "unconnected-(M2-GND-Pad20)") (class "Default")
      (node (ref "M2") (pin "20") (pinfunction "GND_20") (pintype "no_connect"))
    )
    (net (code "83") (name "unconnected-(M2-NRST-Pad17)") (class "Default")
      (node (ref "M2") (pin "17") (pinfunction "NRST_17") (pintype "no_connect"))
    )
    (net (code "84") (name "unconnected-(M2-PA11-Pad33)") (class "Default")
      (node (ref "M2") (pin "33") (pinfunction "PA11_33") (pintype "no_connect"))
    )
    (net (code "85") (name "unconnected-(M2-PA12-Pad32)") (class "Default")
      (node (ref "M2") (pin "32") (pinfunction "PA12_32") (pintype "no_connect"))
    )
    (net (code "86") (name "unconnected-(M2-PC14-Pad3)") (class "Default")
      (node (ref "M2") (pin "3") (pinfunction "PC14_3") (pintype "no_connect"))
    )
    (net (code "87") (name "unconnected-(M2-PC15-Pad4)") (class "Default")
      (node (ref "M2") (pin "4") (pinfunction "PC15_4") (pintype "no_connect"))
    )
    (net (code "88") (name "unconnected-(P3-GPIO0-Pad5)") (class "Default")
      (node (ref "P3") (pin "5") (pinfunction "GPIO0_5") (pintype "no_connect"))
    )
    (net (code "89") (name "unconnected-(P4-Pad1)") (class "Default")
      (node (ref "P4") (pin "1") (pinfunction "1_1") (pintype "no_connect"))
    )
    (net (code "90") (name "unconnected-(P4-Pad6)") (class "Default")
      (node (ref "P4") (pin "6") (pinfunction "6_6") (pintype "no_connect"))
    )
  )
)
